# switch.net
KiCad netlist of a schematic drawn in EAGLE
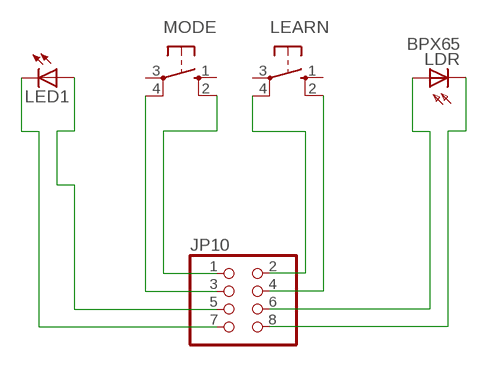
[diagram p0: schematic, sheet 1]

(export (version "E")
  (design (tool "Eeschema 10.0.6"))
  (components
    (comp (ref "JP10")
      (value "PINHD-2X4")
      (footprint "eagle-import:2X04")
      (libsource (lib "eagle-import") (part "PINHD-2X4"))
    )
    (comp (ref "LDR")
      (value "BPX65")
      (footprint "eagle-import:BPX65")
      (fields (field (name "MPN") "BPX65."))
      (libsource (lib "eagle-import") (part "BPX65"))
    )
    (comp (ref "LEARN")
      (value "10-XX")
      (footprint "eagle-import:B3F-10XX")
      (fields (field (name "MPN") "B3F-1000"))
      (libsource (lib "eagle-import") (part "10-XX"))
    )
    (comp (ref "LED1")
      (value "LED3MM")
      (footprint "eagle-import:LED3MM")
      (libsource (lib "eagle-import") (part "LED3MM"))
    )
    (comp (ref "MODE")
      (value "10-XX")
      (footprint "eagle-import:B3F-10XX")
      (fields (field (name "MPN") "B3F-1000"))
      (libsource (lib "eagle-import") (part "10-XX"))
    )
  )
  (nets
    (net (code "1") (name "Net-(JP10-Pad5)") (class "Default")
      (node (ref "JP10") (pin "5") (pinfunction "5_5") (pintype "passive"))
      (node (ref "LED1") (pin "A") (pinfunction "A_A") (pintype "passive"))
    )
    (net (code "2") (name "Net-(JP10-Pad6)") (class "Default")
      (node (ref "JP10") (pin "6") (pinfunction "6_6") (pintype "passive"))
      (node (ref "LDR") (pin "A") (pinfunction "A_A") (pintype "passive"))
    )
    (net (code "3") (name "Net-(LDR-C)") (class "Default")
      (node (ref "JP10") (pin "8") (pinfunction "8_8") (pintype "passive"))
      (node (ref "LDR") (pin "K") (pinfunction "C_K") (pintype "passive"))
    )
    (net (code "4") (name "Net-(LEARN-P1)") (class "Default")
      (node (ref "JP10") (pin "2") (pinfunction "2_2") (pintype "passive"))
      (node (ref "LEARN") (pin "4") (pinfunction "P1_4") (pintype "passive"))
    )
    (net (code "5") (name "Net-(LEARN-S1)") (class "Default")
      (node (ref "JP10") (pin "4") (pinfunction "4_4") (pintype "passive"))
      (node (ref "LEARN") (pin "2") (pinfunction "S1_2") (pintype "passive"))
    )
    (net (code "6") (name "Net-(LED1-C)") (class "Default")
      (node (ref "JP10") (pin "7") (pinfunction "7_7") (pintype "passive"))
      (node (ref "LED1") (pin "K") (pinfunction "C_K") (pintype "passive"))
    )
    (net (code "7") (name "Net-(MODE-P1)") (class "Default")
      (node (ref "JP10") (pin "3") (pinfunction "3_3") (pintype "passive"))
      (node (ref "MODE") (pin "4") (pinfunction "P1_4") (pintype "passive"))
    )
    (net (code "8") (name "Net-(MODE-S1)") (class "Default")
      (node (ref "JP10") (pin "1") (pinfunction "1_1") (pintype "passive"))
      (node (ref "MODE") (pin "2") (pinfunction "S1_2") (pintype "passive"))
    )
    (net (code "9") (name "unconnected-(LEARN-P-Pad3)") (class "Default")
      (node (ref "LEARN") (pin "3") (pinfunction "P_3") (pintype "passive"))
    )
    (net (code "10") (name "unconnected-(LEARN-S-Pad1)") (class "Default")
      (node (ref "LEARN") (pin "1") (pinfunction "S_1") (pintype "passive"))
    )
    (net (code "11") (name "unconnected-(MODE-P-Pad3)") (class "Default")
      (node (ref "MODE") (pin "3") (pinfunction "P_3") (pintype "passive"))
    )
    (net (code "12") (name "unconnected-(MODE-S-Pad1)") (class "Default")
      (node (ref "MODE") (pin "1") (pinfunction "S_1") (pintype "passive"))
    )
  )
)
